# WW-12.net
KiCad netlist of a schematic drawn in EAGLE
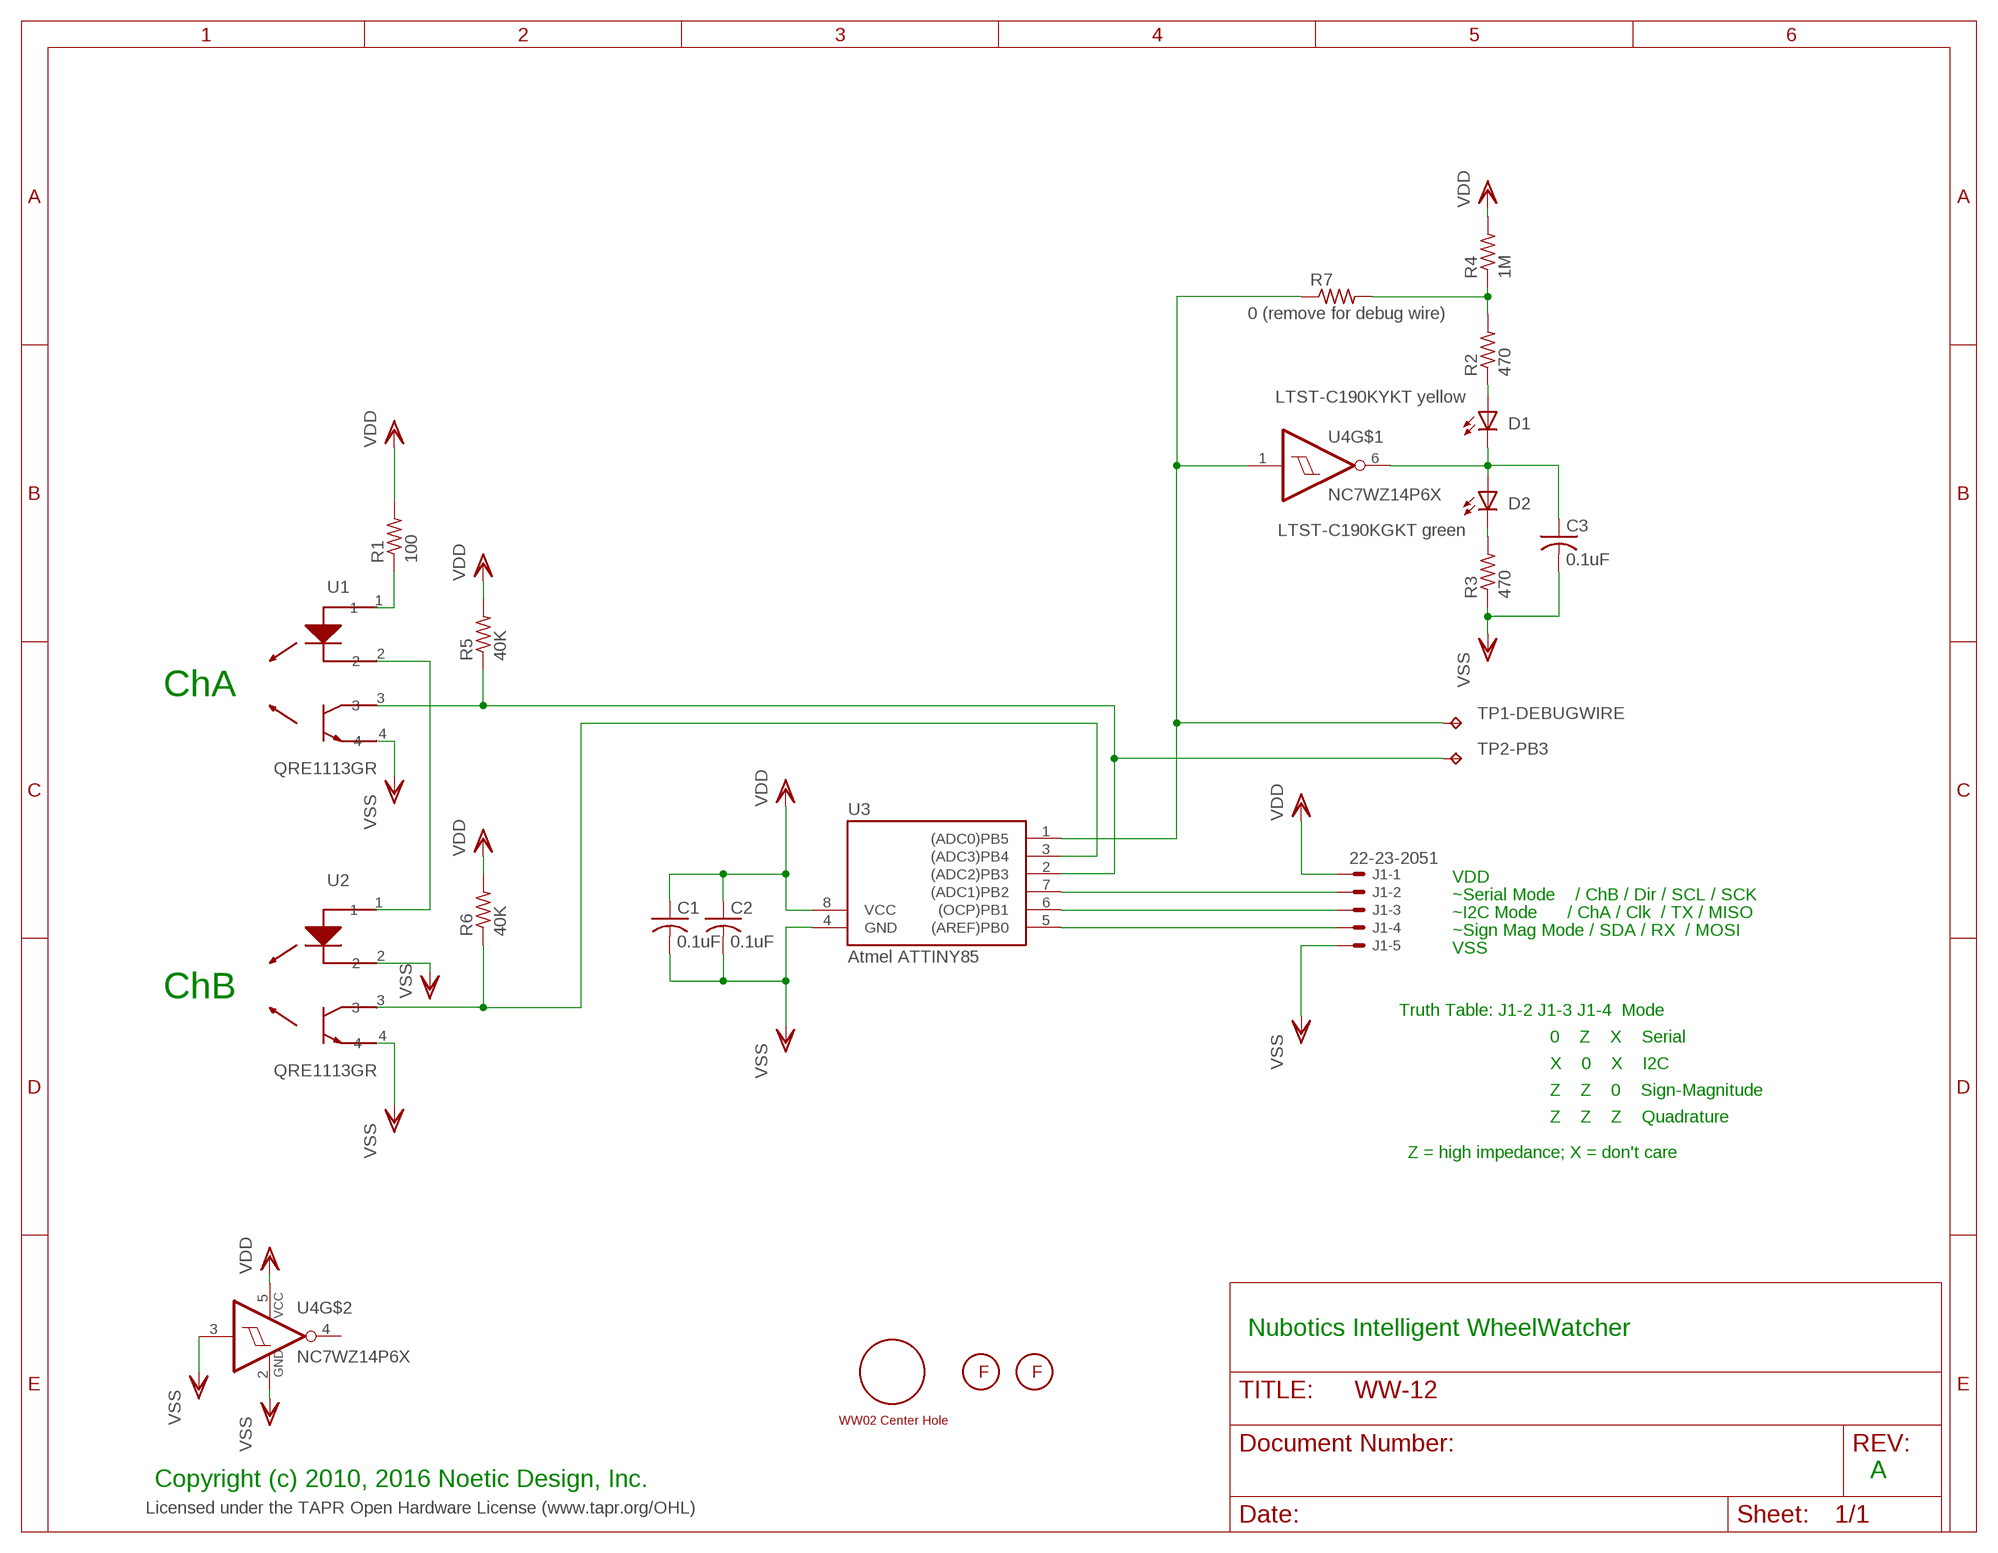
[diagram p0: schematic, sheet 1]

(export (version "E")
  (design (tool "Eeschema 10.0.6"))
  (components
    (comp (ref "C1")
      (value "0.1uF")
      (footprint "eagle-import:C0603")
      (libsource (lib "eagle-import") (part "resistor_C-USC0603"))
    )
    (comp (ref "C2")
      (value "0.1uF")
      (footprint "eagle-import:C0603")
      (libsource (lib "eagle-import") (part "resistor_C-USC0603"))
    )
    (comp (ref "C3")
      (value "0.1uF")
      (footprint "eagle-import:C0603")
      (libsource (lib "eagle-import") (part "C-USC0603"))
    )
    (comp (ref "D1")
      (value "LTST-C190KYKT yellow")
      (footprint "eagle-import:CHIP-LED0603")
      (libsource (lib "eagle-import") (part "LEDCHIP-LED0603"))
    )
    (comp (ref "D2")
      (value "LTST-C190KGKT green")
      (footprint "eagle-import:CHIP-LED0603")
      (libsource (lib "eagle-import") (part "LEDCHIP-LED0603"))
    )
    (comp (ref "FM1")
      (value "FIDUCIAL2MMCIRCLE")
      (footprint "eagle-import:FIDUCIAL_2MMCIRCLE")
      (libsource (lib "eagle-import") (part "FIDUCIAL2MMCIRCLE"))
    )
    (comp (ref "FM2")
      (value "FIDUCIAL2MMCIRCLE")
      (footprint "eagle-import:FIDUCIAL_2MMCIRCLE")
      (libsource (lib "eagle-import") (part "FIDUCIAL2MMCIRCLE"))
    )
    (comp (ref "J1")
      (value "22-23-2051")
      (footprint "eagle-import:22-23-2051")
      (libsource (lib "eagle-import") (part "22-23-2051"))
    )
    (comp (ref "R1")
      (value "100")
      (footprint "eagle-import:R0603")
      (libsource (lib "eagle-import") (part "resistor_R-US_R0603"))
    )
    (comp (ref "R2")
      (value "470")
      (footprint "eagle-import:R0603")
      (libsource (lib "eagle-import") (part "resistor_R-US_R0603"))
    )
    (comp (ref "R3")
      (value "470")
      (footprint "eagle-import:R0603")
      (libsource (lib "eagle-import") (part "resistor_R-US_R0603"))
    )
    (comp (ref "R4")
      (value "1M")
      (footprint "eagle-import:R0603")
      (libsource (lib "eagle-import") (part "R-US_R0603"))
    )
    (comp (ref "R5")
      (value "40K")
      (footprint "eagle-import:R0603")
      (libsource (lib "eagle-import") (part "resistor_R-US_R0603"))
    )
    (comp (ref "R6")
      (value "40K")
      (footprint "eagle-import:R0603")
      (libsource (lib "eagle-import") (part "resistor_R-US_R0603"))
    )
    (comp (ref "R7")
      (value "0 (remove for debug wire)")
      (footprint "eagle-import:R0603")
      (libsource (lib "eagle-import") (part "R-US_R0603"))
    )
    (comp (ref "TP1-DEBUGWIRE")
      (value "DEBUG WIRE")
      (footprint "eagle-import:B1,27")
      (libsource (lib "eagle-import") (part "TPB1,27"))
    )
    (comp (ref "TP2-PB3")
      (value "DEBUG WIRE")
      (footprint "eagle-import:B1,27")
      (libsource (lib "eagle-import") (part "TPB1,27"))
    )
    (comp (ref "U$1")
      (value "WW02-CENTER")
      (footprint "eagle-import:WW02-CENTER")
      (libsource (lib "eagle-import") (part "WW02-CENTER"))
    )
    (comp (ref "U1")
      (value "QRE1113GR")
      (footprint "eagle-import:4TSOP")
      (libsource (lib "eagle-import") (part "QRE1113GR"))
    )
    (comp (ref "U2")
      (value "QRE1113GR")
      (footprint "eagle-import:4TSOP")
      (libsource (lib "eagle-import") (part "QRE1113GR"))
    )
    (comp (ref "U3")
      (value "Atmel ATTINY85")
      (footprint "eagle-import:SOIC8")
      (libsource (lib "eagle-import") (part "TINY85S"))
    )
    (comp (ref "U4")
      (value "NC7WZ14P6X")
      (footprint "eagle-import:SOT65P210X110-6AN_SC88_SC70-6")
      (libsource (lib "eagle-import") (part "NC7W14P6XZ"))
    )
  )
  (nets
    (net (code "1") (name "Net-(D1-PadA)") (class "Default")
      (node (ref "D1") (pin "A") (pinfunction "A_A") (pintype "passive"))
      (node (ref "R2") (pin "1") (pinfunction "1_1") (pintype "passive"))
    )
    (net (code "2") (name "Net-(D2-PadC)") (class "Default")
      (node (ref "D2") (pin "C") (pinfunction "C_C") (pintype "passive"))
      (node (ref "R3") (pin "2") (pinfunction "2_2") (pintype "passive"))
    )
    (net (code "3") (name "Net-(J1B-S)") (class "Default")
      (node (ref "J1") (pin "2") (pinfunction "S_2") (pintype "passive"))
      (node (ref "U3") (pin "7") (pinfunction "(ADC1)PB2_7") (pintype "bidirectional"))
    )
    (net (code "4") (name "Net-(J1C-S)") (class "Default")
      (node (ref "J1") (pin "3") (pinfunction "S_3") (pintype "passive"))
      (node (ref "U3") (pin "6") (pinfunction "(OCP)PB1_6") (pintype "bidirectional"))
    )
    (net (code "5") (name "Net-(J1D-S)") (class "Default")
      (node (ref "J1") (pin "4") (pinfunction "S_4") (pintype "passive"))
      (node (ref "U3") (pin "5") (pinfunction "(AREF)PB0_5") (pintype "bidirectional"))
    )
    (net (code "6") (name "Net-(R1-Pad1)") (class "Default")
      (node (ref "R1") (pin "1") (pinfunction "1_1") (pintype "passive"))
      (node (ref "U1") (pin "1") (pinfunction "1_1") (pintype "bidirectional"))
    )
    (net (code "7") (name "Net-(R2-Pad2)") (class "Default")
      (node (ref "R2") (pin "2") (pinfunction "2_2") (pintype "passive"))
      (node (ref "R4") (pin "1") (pinfunction "1_1") (pintype "passive"))
      (node (ref "R7") (pin "2") (pinfunction "2_2") (pintype "passive"))
    )
    (net (code "8") (name "Net-(U1-Pad2)") (class "Default")
      (node (ref "U1") (pin "2") (pinfunction "2_2") (pintype "bidirectional"))
      (node (ref "U2") (pin "1") (pinfunction "1_1") (pintype "bidirectional"))
    )
    (net (code "9") (name "Net-(U3-(ADC0)PB5)") (class "Default")
      (node (ref "R7") (pin "1") (pinfunction "1_1") (pintype "passive"))
      (node (ref "TP1-DEBUGWIRE") (pin "TP") (pinfunction "TP_TP") (pintype "input"))
      (node (ref "U3") (pin "1") (pinfunction "(ADC0)PB5_1") (pintype "bidirectional"))
      (node (ref "U4") (pin "1") (pinfunction "I_1") (pintype "input"))
    )
    (net (code "10") (name "Net-(U3-(ADC2)PB3)") (class "Default")
      (node (ref "R5") (pin "1") (pinfunction "1_1") (pintype "passive"))
      (node (ref "TP2-PB3") (pin "TP") (pinfunction "TP_TP") (pintype "input"))
      (node (ref "U1") (pin "3") (pinfunction "3_3") (pintype "bidirectional"))
      (node (ref "U3") (pin "2") (pinfunction "(ADC2)PB3_2") (pintype "bidirectional"))
    )
    (net (code "11") (name "Net-(U3-(ADC3)PB4)") (class "Default")
      (node (ref "R6") (pin "1") (pinfunction "1_1") (pintype "passive"))
      (node (ref "U2") (pin "3") (pinfunction "3_3") (pintype "bidirectional"))
      (node (ref "U3") (pin "3") (pinfunction "(ADC3)PB4_3") (pintype "bidirectional"))
    )
    (net (code "12") (name "Net-(U4A-O)") (class "Default")
      (node (ref "C3") (pin "1") (pinfunction "1_1") (pintype "passive"))
      (node (ref "D1") (pin "C") (pinfunction "C_C") (pintype "passive"))
      (node (ref "D2") (pin "A") (pinfunction "A_A") (pintype "passive"))
      (node (ref "U4") (pin "6") (pinfunction "O_6") (pintype "output"))
    )
    (net (code "13") (name "VDD") (class "Default")
      (node (ref "C1") (pin "1") (pinfunction "1_1") (pintype "passive"))
      (node (ref "C2") (pin "1") (pinfunction "1_1") (pintype "passive"))
      (node (ref "J1") (pin "1") (pinfunction "S_1") (pintype "passive"))
      (node (ref "R1") (pin "2") (pinfunction "2_2") (pintype "passive"))
      (node (ref "R4") (pin "2") (pinfunction "2_2") (pintype "passive"))
      (node (ref "R5") (pin "2") (pinfunction "2_2") (pintype "passive"))
      (node (ref "R6") (pin "2") (pinfunction "2_2") (pintype "passive"))
      (node (ref "U3") (pin "8") (pinfunction "VCC_8") (pintype "power_in"))
      (node (ref "U4") (pin "5") (pinfunction "VCC_5") (pintype "power_in"))
    )
    (net (code "14") (name "VSS") (class "Default")
      (node (ref "C1") (pin "2") (pinfunction "2_2") (pintype "passive"))
      (node (ref "C2") (pin "2") (pinfunction "2_2") (pintype "passive"))
      (node (ref "C3") (pin "2") (pinfunction "2_2") (pintype "passive"))
      (node (ref "J1") (pin "5") (pinfunction "S_5") (pintype "passive"))
      (node (ref "R3") (pin "1") (pinfunction "1_1") (pintype "passive"))
      (node (ref "U1") (pin "4") (pinfunction "4_4") (pintype "bidirectional"))
      (node (ref "U2") (pin "2") (pinfunction "2_2") (pintype "bidirectional"))
      (node (ref "U2") (pin "4") (pinfunction "4_4") (pintype "bidirectional"))
      (node (ref "U3") (pin "4") (pinfunction "GND_4") (pintype "power_in"))
      (node (ref "U4") (pin "2") (pinfunction "GND_2") (pintype "power_in"))
      (node (ref "U4") (pin "3") (pinfunction "I_3") (pintype "input"))
    )
    (net (code "15") (name "unconnected-(U4B-O-Pad4)") (class "Default")
      (node (ref "U4") (pin "4") (pinfunction "O_4") (pintype "output"))
    )
  )
)
